# OMNIBUS_Stepper_board_v3.net
KiCad netlist of a schematic drawn in EAGLE
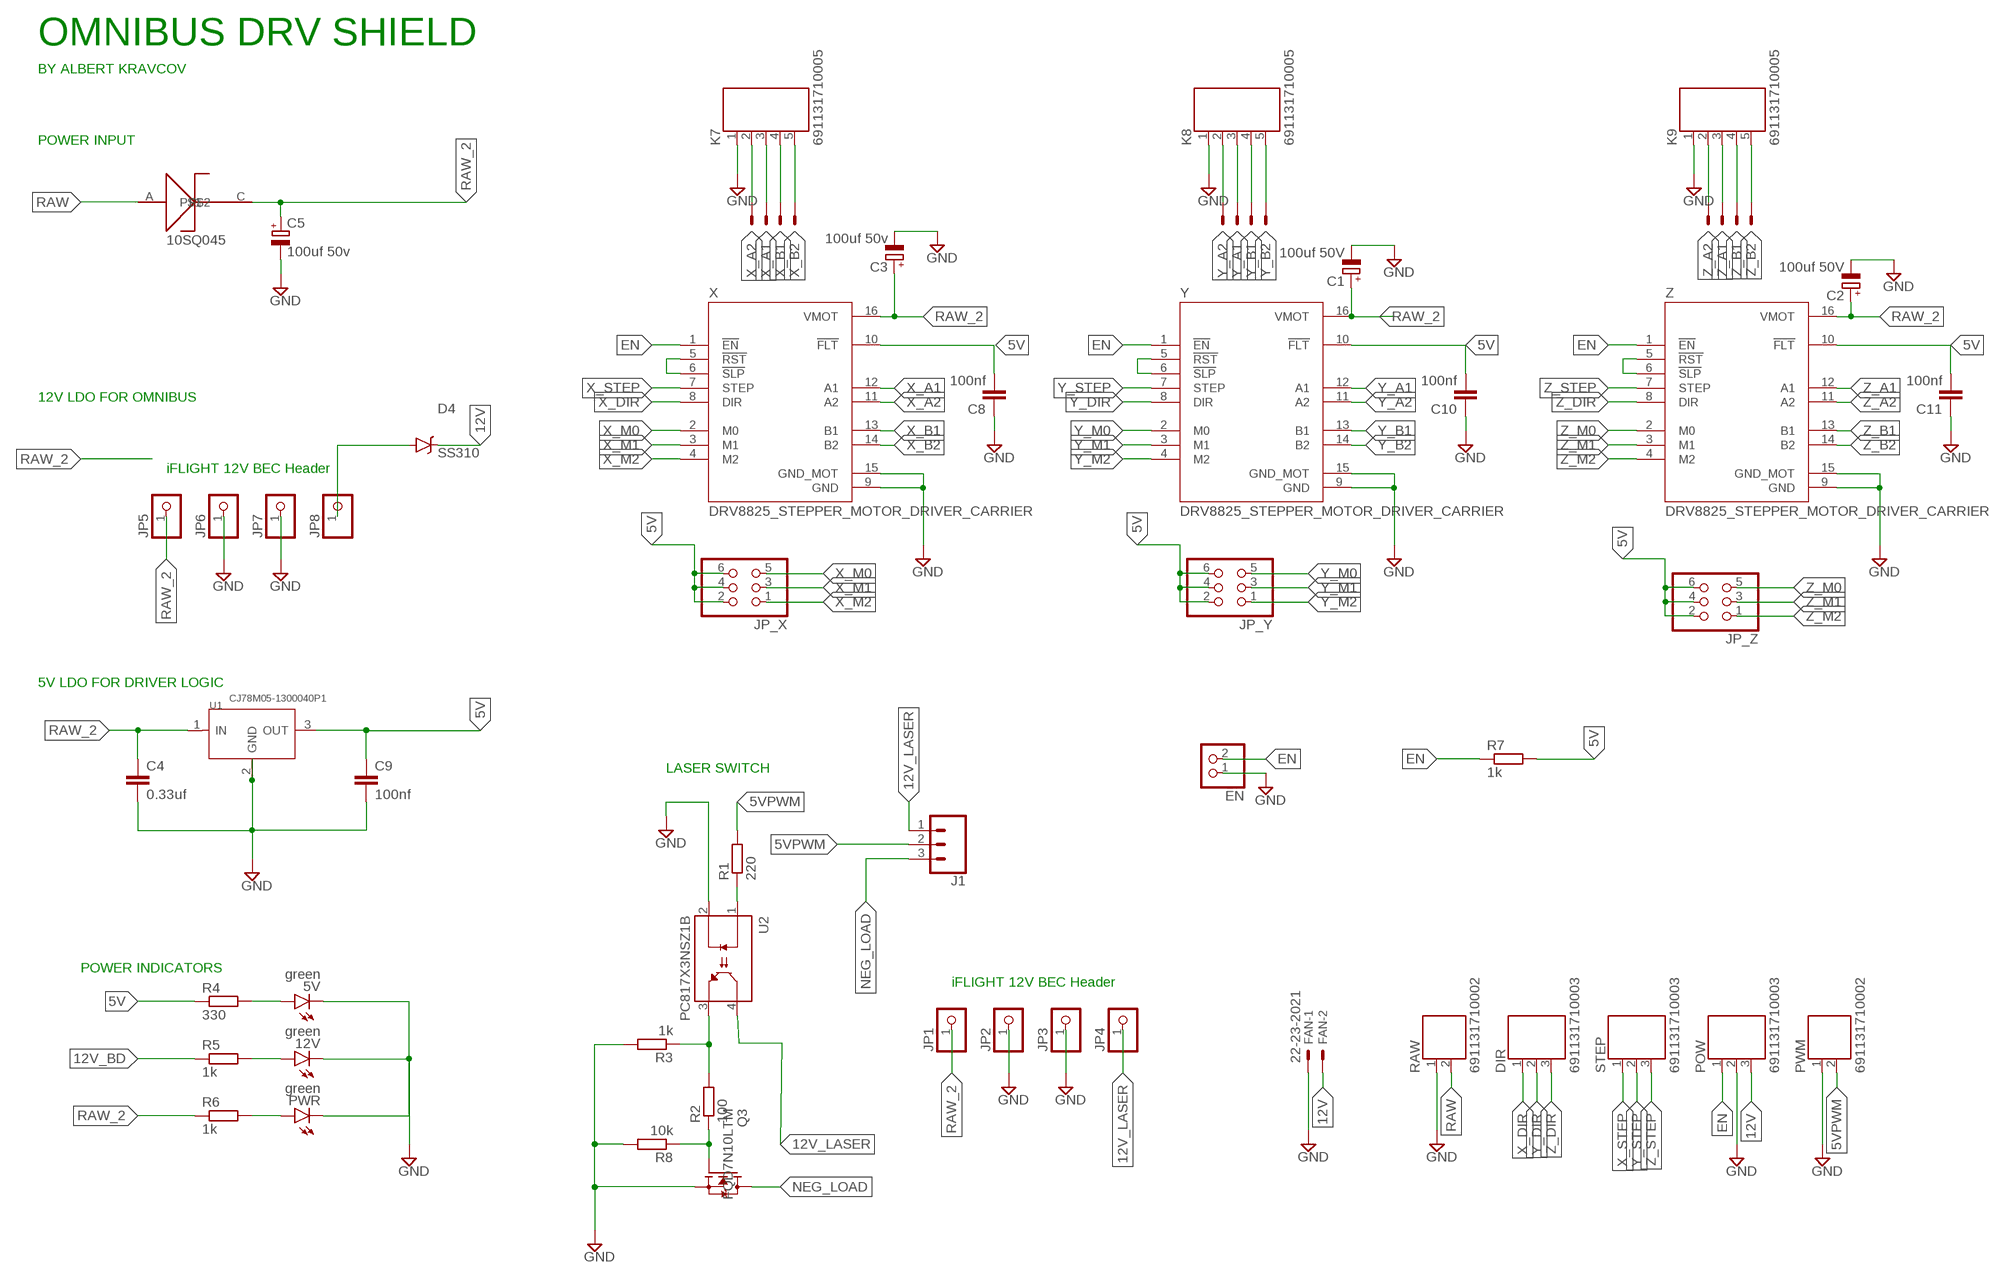
[diagram p0: schematic, sheet 1]

(export (version "E")
  (design (tool "Eeschema 10.0.6"))
  (components
    (comp (ref "5V")
      (value "green")
      (footprint "eagle-import:CHIPLED_0805")
      (libsource (lib "eagle-import") (part "LEDCHIPLED_0805"))
    )
    (comp (ref "12V")
      (value "green")
      (footprint "eagle-import:CHIPLED_0805")
      (libsource (lib "eagle-import") (part "LEDCHIPLED_0805"))
    )
    (comp (ref "C1")
      (value "100uf 50V")
      (footprint "eagle-import:E5-6")
      (libsource (lib "eagle-import") (part "CPOL-EUE5-6"))
    )
    (comp (ref "C2")
      (value "100uf 50V")
      (footprint "eagle-import:E5-6")
      (libsource (lib "eagle-import") (part "CPOL-EUE5-6"))
    )
    (comp (ref "C3")
      (value "100uf 50v")
      (footprint "eagle-import:E5-6")
      (libsource (lib "eagle-import") (part "CPOL-EUE5-6"))
    )
    (comp (ref "C4")
      (value "0.33uf")
      (footprint "eagle-import:C1206")
      (libsource (lib "eagle-import") (part "C-EUC1206"))
    )
    (comp (ref "C5")
      (value "100uf 50v")
      (footprint "eagle-import:E5-8,5")
      (libsource (lib "eagle-import") (part "rcl_334_CPOL-EUE5-8.5"))
    )
    (comp (ref "C8")
      (value "100nf")
      (footprint "eagle-import:C0805")
      (libsource (lib "eagle-import") (part "C-EUC0805"))
    )
    (comp (ref "C9")
      (value "100nf")
      (footprint "eagle-import:C1206")
      (libsource (lib "eagle-import") (part "C-EUC1206"))
    )
    (comp (ref "C10")
      (value "100nf")
      (footprint "eagle-import:C0805")
      (libsource (lib "eagle-import") (part "C-EUC0805"))
    )
    (comp (ref "C11")
      (value "100nf")
      (footprint "eagle-import:C0805")
      (libsource (lib "eagle-import") (part "C-EUC0805"))
    )
    (comp (ref "D1")
      (value "10SQ045")
      (footprint "eagle-import:DIOAD885W125L910D885")
      (libsource (lib "eagle-import") (part "10SQ050"))
    )
    (comp (ref "D4")
      (value "SS310")
      (footprint "eagle-import:DO-214AC")
      (fields (field (name "MF") "Honeywell Sensing") (field (name "MP") "SS54"))
      (libsource (lib "eagle-import") (part "SS54"))
    )
    (comp (ref "DIR")
      (value "691131710003")
      (footprint "eagle-import:691131710003")
      (libsource (lib "eagle-import") (part "691131710003"))
    )
    (comp (ref "EN")
      (value "PINHD-1X2")
      (footprint "eagle-import:1X02")
      (libsource (lib "eagle-import") (part "PINHD-1X2"))
    )
    (comp (ref "FAN")
      (value "22-23-2021")
      (footprint "eagle-import:22-23-2021")
      (fields (field (name "MF") "MOLEX"))
      (libsource (lib "eagle-import") (part "22-23-2021"))
    )
    (comp (ref "J1")
      (value "CONN_03")
      (footprint "eagle-import:1X03")
      (libsource (lib "eagle-import") (part "CONN_03"))
    )
    (comp (ref "JP1")
      (value "PINHD-1X1")
      (footprint "eagle-import:1X01")
      (libsource (lib "eagle-import") (part "PINHD-1X1"))
    )
    (comp (ref "JP2")
      (value "PINHD-1X1")
      (footprint "eagle-import:1X01")
      (libsource (lib "eagle-import") (part "PINHD-1X1"))
    )
    (comp (ref "JP3")
      (value "PINHD-1X1")
      (footprint "eagle-import:1X01")
      (libsource (lib "eagle-import") (part "PINHD-1X1"))
    )
    (comp (ref "JP4")
      (value "PINHD-1X1")
      (footprint "eagle-import:1X01")
      (libsource (lib "eagle-import") (part "PINHD-1X1"))
    )
    (comp (ref "JP5")
      (value "PINHD-1X1")
      (footprint "eagle-import:1X01")
      (libsource (lib "eagle-import") (part "PINHD-1X1"))
    )
    (comp (ref "JP6")
      (value "PINHD-1X1")
      (footprint "eagle-import:1X01")
      (libsource (lib "eagle-import") (part "PINHD-1X1"))
    )
    (comp (ref "JP7")
      (value "PINHD-1X1")
      (footprint "eagle-import:1X01")
      (libsource (lib "eagle-import") (part "PINHD-1X1"))
    )
    (comp (ref "JP8")
      (value "PINHD-1X1")
      (footprint "eagle-import:1X01")
      (libsource (lib "eagle-import") (part "PINHD-1X1"))
    )
    (comp (ref "JP_X")
      (value "PINHD-2X3")
      (footprint "eagle-import:2X03")
      (libsource (lib "eagle-import") (part "PINHD-2X3"))
    )
    (comp (ref "JP_Y")
      (value "PINHD-2X3")
      (footprint "eagle-import:2X03")
      (libsource (lib "eagle-import") (part "PINHD-2X3"))
    )
    (comp (ref "JP_Z")
      (value "PINHD-2X3")
      (footprint "eagle-import:2X03")
      (libsource (lib "eagle-import") (part "PINHD-2X3"))
    )
    (comp (ref "K7")
      (value "691131710005")
      (footprint "eagle-import:691131710005")
      (libsource (lib "eagle-import") (part "691131710005"))
    )
    (comp (ref "K8")
      (value "691131710005")
      (footprint "eagle-import:691131710005")
      (libsource (lib "eagle-import") (part "691131710005"))
    )
    (comp (ref "K9")
      (value "691131710005")
      (footprint "eagle-import:691131710005")
      (libsource (lib "eagle-import") (part "691131710005"))
    )
    (comp (ref "POW")
      (value "691131710003")
      (footprint "eagle-import:691131710003")
      (libsource (lib "eagle-import") (part "691131710003"))
    )
    (comp (ref "PWM")
      (value "691131710002")
      (footprint "eagle-import:691131710002")
      (libsource (lib "eagle-import") (part "691131710002"))
    )
    (comp (ref "PWR")
      (value "green")
      (footprint "eagle-import:CHIPLED_0805")
      (libsource (lib "eagle-import") (part "LEDCHIPLED_0805"))
    )
    (comp (ref "Q3")
      (value "FQD7N10LTM")
      (footprint "eagle-import:TO-252")
      (fields (field (name "MF") "ON Semiconductor"))
      (libsource (lib "eagle-import") (part "FQD7N10LTM"))
    )
    (comp (ref "R1")
      (value "220")
      (footprint "eagle-import:R0805")
      (libsource (lib "eagle-import") (part "R-EU_R0805"))
    )
    (comp (ref "R2")
      (value "100")
      (footprint "eagle-import:R0805")
      (libsource (lib "eagle-import") (part "R-EU_R0805"))
    )
    (comp (ref "R3")
      (value "1k")
      (footprint "eagle-import:R0805")
      (libsource (lib "eagle-import") (part "R-EU_R0805"))
    )
    (comp (ref "R4")
      (value "330")
      (footprint "eagle-import:R0805")
      (libsource (lib "eagle-import") (part "R-EU_R0805"))
    )
    (comp (ref "R5")
      (value "1k")
      (footprint "eagle-import:R0805")
      (libsource (lib "eagle-import") (part "R-EU_R0805"))
    )
    (comp (ref "R6")
      (value "1k")
      (footprint "eagle-import:R1206")
      (libsource (lib "eagle-import") (part "R-EU_R1206"))
    )
    (comp (ref "R7")
      (value "1k")
      (footprint "eagle-import:R0805")
      (libsource (lib "eagle-import") (part "R-EU_R0805"))
    )
    (comp (ref "R8")
      (value "10k")
      (footprint "eagle-import:R0805")
      (libsource (lib "eagle-import") (part "R-EU_R0805"))
    )
    (comp (ref "RAW")
      (value "691131710002")
      (footprint "eagle-import:691131710002")
      (libsource (lib "eagle-import") (part "691131710002"))
    )
    (comp (ref "STEP")
      (value "691131710003")
      (footprint "eagle-import:691131710003")
      (libsource (lib "eagle-import") (part "691131710003"))
    )
    (comp (ref "U1")
      (value "CJ78M05-1300040P1")
      (footprint "eagle-import:TO252")
      (fields (field (name "MF") "JCET") (field (name "MP") "CJ78M05"))
      (libsource (lib "eagle-import") (part "CJ78M05-1300040P1"))
    )
    (comp (ref "U2")
      (value "PC817X3NSZ1B")
      (footprint "eagle-import:DIP762W50P254L495H455Q4")
      (fields (field (name "MF") "Sharp Microelectronics"))
      (libsource (lib "eagle-import") (part "PC817X3NSZ1B"))
    )
    (comp (ref "X")
      (value "DRV8825_STEPPER_MOTOR_DRIVER_CARRIER")
      (footprint "eagle-import:IC_DRV8825_STEPPER_MOTOR_DRIVER_CARRIER")
      (fields (field (name "MF") "Pololu") (field (name "MP") "DRV8825 STEPPER MOTOR DRIVER CARRIER"))
      (libsource (lib "eagle-import") (part "DRV8825_STEPPER_MOTOR_DRIVER_CARRIER"))
    )
    (comp (ref "X_MOTOR")
      (value "22-23-2041")
      (footprint "eagle-import:22-23-2041")
      (fields (field (name "MF") "MOLEX"))
      (libsource (lib "eagle-import") (part "22-23-2041"))
    )
    (comp (ref "Y")
      (value "DRV8825_STEPPER_MOTOR_DRIVER_CARRIER")
      (footprint "eagle-import:IC_DRV8825_STEPPER_MOTOR_DRIVER_CARRIER")
      (fields (field (name "MF") "Pololu") (field (name "MP") "DRV8825 STEPPER MOTOR DRIVER CARRIER"))
      (libsource (lib "eagle-import") (part "DRV8825_STEPPER_MOTOR_DRIVER_CARRIER"))
    )
    (comp (ref "Y_MOTOR")
      (value "22-23-2041")
      (footprint "eagle-import:22-23-2041")
      (fields (field (name "MF") "MOLEX"))
      (libsource (lib "eagle-import") (part "22-23-2041"))
    )
    (comp (ref "Z")
      (value "DRV8825_STEPPER_MOTOR_DRIVER_CARRIER")
      (footprint "eagle-import:IC_DRV8825_STEPPER_MOTOR_DRIVER_CARRIER")
      (fields (field (name "MF") "Pololu") (field (name "MP") "DRV8825 STEPPER MOTOR DRIVER CARRIER"))
      (libsource (lib "eagle-import") (part "DRV8825_STEPPER_MOTOR_DRIVER_CARRIER"))
    )
    (comp (ref "Z_MOTOR")
      (value "22-23-2041")
      (footprint "eagle-import:22-23-2041")
      (fields (field (name "MF") "MOLEX"))
      (libsource (lib "eagle-import") (part "22-23-2041"))
    )
  )
  (nets
    (net (code "1") (name "5V") (class "Default")
      (node (ref "C10") (pin "2") (pinfunction "2_2") (pintype "passive"))
      (node (ref "C11") (pin "2") (pinfunction "2_2") (pintype "passive"))
      (node (ref "C8") (pin "2") (pinfunction "2_2") (pintype "passive"))
      (node (ref "C9") (pin "1") (pinfunction "1_1") (pintype "passive"))
      (node (ref "JP_X") (pin "2") (pinfunction "2_2") (pintype "passive"))
      (node (ref "JP_X") (pin "4") (pinfunction "4_4") (pintype "passive"))
      (node (ref "JP_X") (pin "6") (pinfunction "6_6") (pintype "passive"))
      (node (ref "JP_Y") (pin "2") (pinfunction "2_2") (pintype "passive"))
      (node (ref "JP_Y") (pin "4") (pinfunction "4_4") (pintype "passive"))
      (node (ref "JP_Y") (pin "6") (pinfunction "6_6") (pintype "passive"))
      (node (ref "JP_Z") (pin "2") (pinfunction "2_2") (pintype "passive"))
      (node (ref "JP_Z") (pin "4") (pinfunction "4_4") (pintype "passive"))
      (node (ref "JP_Z") (pin "6") (pinfunction "6_6") (pintype "passive"))
      (node (ref "R4") (pin "1") (pinfunction "1_1") (pintype "passive"))
      (node (ref "R7") (pin "2") (pinfunction "2_2") (pintype "passive"))
      (node (ref "U1") (pin "3") (pinfunction "OUT_3") (pintype "bidirectional"))
      (node (ref "X") (pin "10") (pinfunction "~{FLT}_10") (pintype "output"))
      (node (ref "Y") (pin "10") (pinfunction "~{FLT}_10") (pintype "output"))
      (node (ref "Z") (pin "10") (pinfunction "~{FLT}_10") (pintype "output"))
    )
    (net (code "2") (name "5VPWM") (class "Default")
      (node (ref "J1") (pin "2") (pinfunction "2_2") (pintype "passive"))
      (node (ref "PWM") (pin "2") (pinfunction "2_2") (pintype "passive"))
      (node (ref "R1") (pin "2") (pinfunction "2_2") (pintype "passive"))
    )
    (net (code "3") (name "12V") (class "Default")
      (node (ref "D4") (pin "C") (pinfunction "C_C") (pintype "passive"))
      (node (ref "FAN") (pin "2") (pinfunction "S_2") (pintype "passive"))
      (node (ref "POW") (pin "3") (pinfunction "3_3") (pintype "passive"))
    )
    (net (code "4") (name "12V_BD") (class "Default")
      (node (ref "D4") (pin "A") (pinfunction "A_A") (pintype "passive"))
      (node (ref "JP8") (pin "1") (pinfunction "1_1") (pintype "passive"))
      (node (ref "R5") (pin "1") (pinfunction "1_1") (pintype "passive"))
    )
    (net (code "5") (name "12V_LASER") (class "Default")
      (node (ref "J1") (pin "1") (pinfunction "1_1") (pintype "passive"))
      (node (ref "JP4") (pin "1") (pinfunction "1_1") (pintype "passive"))
      (node (ref "U2") (pin "4") (pinfunction "COLLECTOR_4") (pintype "passive"))
    )
    (net (code "6") (name "EN") (class "Default")
      (node (ref "EN") (pin "2") (pinfunction "2_2") (pintype "passive"))
      (node (ref "POW") (pin "1") (pinfunction "1_1") (pintype "passive"))
      (node (ref "R7") (pin "1") (pinfunction "1_1") (pintype "passive"))
      (node (ref "X") (pin "1") (pinfunction "~{EN}_1") (pintype "input"))
      (node (ref "Y") (pin "1") (pinfunction "~{EN}_1") (pintype "input"))
      (node (ref "Z") (pin "1") (pinfunction "~{EN}_1") (pintype "input"))
    )
    (net (code "7") (name "GND") (class "Default")
      (node (ref "12V") (pin "C") (pinfunction "C_C") (pintype "passive"))
      (node (ref "5V") (pin "C") (pinfunction "C_C") (pintype "passive"))
      (node (ref "C1") (pin "-") (pinfunction "-_-") (pintype "passive"))
      (node (ref "C10") (pin "1") (pinfunction "1_1") (pintype "passive"))
      (node (ref "C11") (pin "1") (pinfunction "1_1") (pintype "passive"))
      (node (ref "C2") (pin "-") (pinfunction "-_-") (pintype "passive"))
      (node (ref "C3") (pin "-") (pinfunction "-_-") (pintype "passive"))
      (node (ref "C4") (pin "2") (pinfunction "2_2") (pintype "passive"))
      (node (ref "C5") (pin "-") (pinfunction "-_-") (pintype "passive"))
      (node (ref "C8") (pin "1") (pinfunction "1_1") (pintype "passive"))
      (node (ref "C9") (pin "2") (pinfunction "2_2") (pintype "passive"))
      (node (ref "EN") (pin "1") (pinfunction "1_1") (pintype "passive"))
      (node (ref "FAN") (pin "1") (pinfunction "S_1") (pintype "passive"))
      (node (ref "JP2") (pin "1") (pinfunction "1_1") (pintype "passive"))
      (node (ref "JP3") (pin "1") (pinfunction "1_1") (pintype "passive"))
      (node (ref "JP6") (pin "1") (pinfunction "1_1") (pintype "passive"))
      (node (ref "JP7") (pin "1") (pinfunction "1_1") (pintype "passive"))
      (node (ref "K7") (pin "1") (pinfunction "1_1") (pintype "passive"))
      (node (ref "K8") (pin "1") (pinfunction "1_1") (pintype "passive"))
      (node (ref "K9") (pin "1") (pinfunction "1_1") (pintype "passive"))
      (node (ref "POW") (pin "2") (pinfunction "2_2") (pintype "passive"))
      (node (ref "PWM") (pin "1") (pinfunction "1_1") (pintype "passive"))
      (node (ref "PWR") (pin "C") (pinfunction "C_C") (pintype "passive"))
      (node (ref "Q3") (pin "3") (pinfunction "S_3") (pintype "passive"))
      (node (ref "R3") (pin "2") (pinfunction "2_2") (pintype "passive"))
      (node (ref "R8") (pin "2") (pinfunction "2_2") (pintype "passive"))
      (node (ref "RAW") (pin "1") (pinfunction "1_1") (pintype "passive"))
      (node (ref "U1") (pin "2") (pinfunction "GND_2") (pintype "bidirectional"))
      (node (ref "U2") (pin "2") (pinfunction "CATHODE_2") (pintype "passive"))
      (node (ref "X") (pin "15") (pinfunction "GND_MOT_15") (pintype "power_in"))
      (node (ref "X") (pin "9") (pinfunction "GND_9") (pintype "power_in"))
      (node (ref "Y") (pin "15") (pinfunction "GND_MOT_15") (pintype "power_in"))
      (node (ref "Y") (pin "9") (pinfunction "GND_9") (pintype "power_in"))
      (node (ref "Z") (pin "15") (pinfunction "GND_MOT_15") (pintype "power_in"))
      (node (ref "Z") (pin "9") (pinfunction "GND_9") (pintype "power_in"))
    )
    (net (code "8") (name "NEG_LOAD") (class "Default")
      (node (ref "J1") (pin "3") (pinfunction "3_3") (pintype "passive"))
      (node (ref "Q3") (pin "T") (pinfunction "D_T") (pintype "passive"))
    )
    (net (code "9") (name "Net-(5V-PadA)") (class "Default")
      (node (ref "5V") (pin "A") (pinfunction "A_A") (pintype "passive"))
      (node (ref "R4") (pin "2") (pinfunction "2_2") (pintype "passive"))
    )
    (net (code "10") (name "Net-(12V-PadA)") (class "Default")
      (node (ref "12V") (pin "A") (pinfunction "A_A") (pintype "passive"))
      (node (ref "R5") (pin "2") (pinfunction "2_2") (pintype "passive"))
    )
    (net (code "11") (name "Net-(PWR-PadA)") (class "Default")
      (node (ref "PWR") (pin "A") (pinfunction "A_A") (pintype "passive"))
      (node (ref "R6") (pin "2") (pinfunction "2_2") (pintype "passive"))
    )
    (net (code "12") (name "Net-(Q3-G)") (class "Default")
      (node (ref "Q3") (pin "1") (pinfunction "G_1") (pintype "passive"))
      (node (ref "R2") (pin "1") (pinfunction "1_1") (pintype "passive"))
      (node (ref "R8") (pin "1") (pinfunction "1_1") (pintype "passive"))
    )
    (net (code "13") (name "Net-(U2-ANODE)") (class "Default")
      (node (ref "R1") (pin "1") (pinfunction "1_1") (pintype "passive"))
      (node (ref "U2") (pin "1") (pinfunction "ANODE_1") (pintype "passive"))
    )
    (net (code "14") (name "Net-(U2-EMITTER)") (class "Default")
      (node (ref "R2") (pin "2") (pinfunction "2_2") (pintype "passive"))
      (node (ref "R3") (pin "1") (pinfunction "1_1") (pintype "passive"))
      (node (ref "U2") (pin "3") (pinfunction "EMITTER_3") (pintype "passive"))
    )
    (net (code "15") (name "Net-(X-~{RST})") (class "Default")
      (node (ref "X") (pin "5") (pinfunction "~{RST}_5") (pintype "input"))
      (node (ref "X") (pin "6") (pinfunction "~{SLP}_6") (pintype "input"))
    )
    (net (code "16") (name "Net-(Y-~{RST})") (class "Default")
      (node (ref "Y") (pin "5") (pinfunction "~{RST}_5") (pintype "input"))
      (node (ref "Y") (pin "6") (pinfunction "~{SLP}_6") (pintype "input"))
    )
    (net (code "17") (name "Net-(Z-~{RST})") (class "Default")
      (node (ref "Z") (pin "5") (pinfunction "~{RST}_5") (pintype "input"))
      (node (ref "Z") (pin "6") (pinfunction "~{SLP}_6") (pintype "input"))
    )
    (net (code "18") (name "RAW") (class "Default")
      (node (ref "D1") (pin "A") (pinfunction "P$1_A") (pintype "bidirectional"))
      (node (ref "RAW") (pin "2") (pinfunction "2_2") (pintype "passive"))
    )
    (net (code "19") (name "RAW_2") (class "Default")
      (node (ref "C1") (pin "+") (pinfunction "+_+") (pintype "passive"))
      (node (ref "C2") (pin "+") (pinfunction "+_+") (pintype "passive"))
      (node (ref "C3") (pin "+") (pinfunction "+_+") (pintype "passive"))
      (node (ref "C4") (pin "1") (pinfunction "1_1") (pintype "passive"))
      (node (ref "C5") (pin "+") (pinfunction "+_+") (pintype "passive"))
      (node (ref "D1") (pin "C") (pinfunction "P$2_C") (pintype "bidirectional"))
      (node (ref "JP1") (pin "1") (pinfunction "1_1") (pintype "passive"))
      (node (ref "JP5") (pin "1") (pinfunction "1_1") (pintype "passive"))
      (node (ref "R6") (pin "1") (pinfunction "1_1") (pintype "passive"))
      (node (ref "U1") (pin "1") (pinfunction "IN_1") (pintype "bidirectional"))
      (node (ref "X") (pin "16") (pinfunction "VMOT_16") (pintype "power_in"))
      (node (ref "Y") (pin "16") (pinfunction "VMOT_16") (pintype "power_in"))
      (node (ref "Z") (pin "16") (pinfunction "VMOT_16") (pintype "power_in"))
    )
    (net (code "20") (name "X_A1") (class "Default")
      (node (ref "K7") (pin "3") (pinfunction "3_3") (pintype "passive"))
      (node (ref "X") (pin "12") (pinfunction "A1_12") (pintype "output"))
      (node (ref "X_MOTOR") (pin "3") (pinfunction "S_3") (pintype "passive"))
    )
    (net (code "21") (name "X_A2") (class "Default")
      (node (ref "K7") (pin "2") (pinfunction "2_2") (pintype "passive"))
      (node (ref "X") (pin "11") (pinfunction "A2_11") (pintype "output"))
      (node (ref "X_MOTOR") (pin "4") (pinfunction "S_4") (pintype "passive"))
    )
    (net (code "22") (name "X_B1") (class "Default")
      (node (ref "K7") (pin "4") (pinfunction "4_4") (pintype "passive"))
      (node (ref "X") (pin "13") (pinfunction "B1_13") (pintype "output"))
      (node (ref "X_MOTOR") (pin "2") (pinfunction "S_2") (pintype "passive"))
    )
    (net (code "23") (name "X_B2") (class "Default")
      (node (ref "K7") (pin "5") (pinfunction "5_5") (pintype "passive"))
      (node (ref "X") (pin "14") (pinfunction "B2_14") (pintype "output"))
      (node (ref "X_MOTOR") (pin "1") (pinfunction "S_1") (pintype "passive"))
    )
    (net (code "24") (name "X_DIR") (class "Default")
      (node (ref "DIR") (pin "1") (pinfunction "1_1") (pintype "passive"))
      (node (ref "X") (pin "8") (pinfunction "DIR_8") (pintype "input"))
    )
    (net (code "25") (name "X_M0") (class "Default")
      (node (ref "JP_X") (pin "5") (pinfunction "5_5") (pintype "passive"))
      (node (ref "X") (pin "2") (pinfunction "M0_2") (pintype "input"))
    )
    (net (code "26") (name "X_M1") (class "Default")
      (node (ref "JP_X") (pin "3") (pinfunction "3_3") (pintype "passive"))
      (node (ref "X") (pin "3") (pinfunction "M1_3") (pintype "input"))
    )
    (net (code "27") (name "X_M2") (class "Default")
      (node (ref "JP_X") (pin "1") (pinfunction "1_1") (pintype "passive"))
      (node (ref "X") (pin "4") (pinfunction "M2_4") (pintype "input"))
    )
    (net (code "28") (name "X_STEP") (class "Default")
      (node (ref "STEP") (pin "1") (pinfunction "1_1") (pintype "passive"))
      (node (ref "X") (pin "7") (pinfunction "STEP_7") (pintype "input"))
    )
    (net (code "29") (name "Y_A1") (class "Default")
      (node (ref "K8") (pin "3") (pinfunction "3_3") (pintype "passive"))
      (node (ref "Y") (pin "12") (pinfunction "A1_12") (pintype "output"))
      (node (ref "Y_MOTOR") (pin "3") (pinfunction "S_3") (pintype "passive"))
    )
    (net (code "30") (name "Y_A2") (class "Default")
      (node (ref "K8") (pin "2") (pinfunction "2_2") (pintype "passive"))
      (node (ref "Y") (pin "11") (pinfunction "A2_11") (pintype "output"))
      (node (ref "Y_MOTOR") (pin "4") (pinfunction "S_4") (pintype "passive"))
    )
    (net (code "31") (name "Y_B1") (class "Default")
      (node (ref "K8") (pin "4") (pinfunction "4_4") (pintype "passive"))
      (node (ref "Y") (pin "13") (pinfunction "B1_13") (pintype "output"))
      (node (ref "Y_MOTOR") (pin "2") (pinfunction "S_2") (pintype "passive"))
    )
    (net (code "32") (name "Y_B2") (class "Default")
      (node (ref "K8") (pin "5") (pinfunction "5_5") (pintype "passive"))
      (node (ref "Y") (pin "14") (pinfunction "B2_14") (pintype "output"))
      (node (ref "Y_MOTOR") (pin "1") (pinfunction "S_1") (pintype "passive"))
    )
    (net (code "33") (name "Y_DIR") (class "Default")
      (node (ref "DIR") (pin "2") (pinfunction "2_2") (pintype "passive"))
      (node (ref "Y") (pin "8") (pinfunction "DIR_8") (pintype "input"))
    )
    (net (code "34") (name "Y_M0") (class "Default")
      (node (ref "JP_Y") (pin "5") (pinfunction "5_5") (pintype "passive"))
      (node (ref "Y") (pin "2") (pinfunction "M0_2") (pintype "input"))
    )
    (net (code "35") (name "Y_M1") (class "Default")
      (node (ref "JP_Y") (pin "3") (pinfunction "3_3") (pintype "passive"))
      (node (ref "Y") (pin "3") (pinfunction "M1_3") (pintype "input"))
    )
    (net (code "36") (name "Y_M2") (class "Default")
      (node (ref "JP_Y") (pin "1") (pinfunction "1_1") (pintype "passive"))
      (node (ref "Y") (pin "4") (pinfunction "M2_4") (pintype "input"))
    )
    (net (code "37") (name "Y_STEP") (class "Default")
      (node (ref "STEP") (pin "2") (pinfunction "2_2") (pintype "passive"))
      (node (ref "Y") (pin "7") (pinfunction "STEP_7") (pintype "input"))
    )
    (net (code "38") (name "Z_A1") (class "Default")
      (node (ref "K9") (pin "3") (pinfunction "3_3") (pintype "passive"))
      (node (ref "Z") (pin "12") (pinfunction "A1_12") (pintype "output"))
      (node (ref "Z_MOTOR") (pin "3") (pinfunction "S_3") (pintype "passive"))
    )
    (net (code "39") (name "Z_A2") (class "Default")
      (node (ref "K9") (pin "2") (pinfunction "2_2") (pintype "passive"))
      (node (ref "Z") (pin "11") (pinfunction "A2_11") (pintype "output"))
      (node (ref "Z_MOTOR") (pin "4") (pinfunction "S_4") (pintype "passive"))
    )
    (net (code "40") (name "Z_B1") (class "Default")
      (node (ref "K9") (pin "4") (pinfunction "4_4") (pintype "passive"))
      (node (ref "Z") (pin "13") (pinfunction "B1_13") (pintype "output"))
      (node (ref "Z_MOTOR") (pin "2") (pinfunction "S_2") (pintype "passive"))
    )
    (net (code "41") (name "Z_B2") (class "Default")
      (node (ref "K9") (pin "5") (pinfunction "5_5") (pintype "passive"))
      (node (ref "Z") (pin "14") (pinfunction "B2_14") (pintype "output"))
      (node (ref "Z_MOTOR") (pin "1") (pinfunction "S_1") (pintype "passive"))
    )
    (net (code "42") (name "Z_DIR") (class "Default")
      (node (ref "DIR") (pin "3") (pinfunction "3_3") (pintype "passive"))
      (node (ref "Z") (pin "8") (pinfunction "DIR_8") (pintype "input"))
    )
    (net (code "43") (name "Z_M0") (class "Default")
      (node (ref "JP_Z") (pin "5") (pinfunction "5_5") (pintype "passive"))
      (node (ref "Z") (pin "2") (pinfunction "M0_2") (pintype "input"))
    )
    (net (code "44") (name "Z_M1") (class "Default")
      (node (ref "JP_Z") (pin "3") (pinfunction "3_3") (pintype "passive"))
      (node (ref "Z") (pin "3") (pinfunction "M1_3") (pintype "input"))
    )
    (net (code "45") (name "Z_M2") (class "Default")
      (node (ref "JP_Z") (pin "1") (pinfunction "1_1") (pintype "passive"))
      (node (ref "Z") (pin "4") (pinfunction "M2_4") (pintype "input"))
    )
    (net (code "46") (name "Z_STEP") (class "Default")
      (node (ref "STEP") (pin "3") (pinfunction "3_3") (pintype "passive"))
      (node (ref "Z") (pin "7") (pinfunction "STEP_7") (pintype "input"))
    )
  )
)
